# Main.net
KiCad netlist of a schematic drawn in Altium Designer
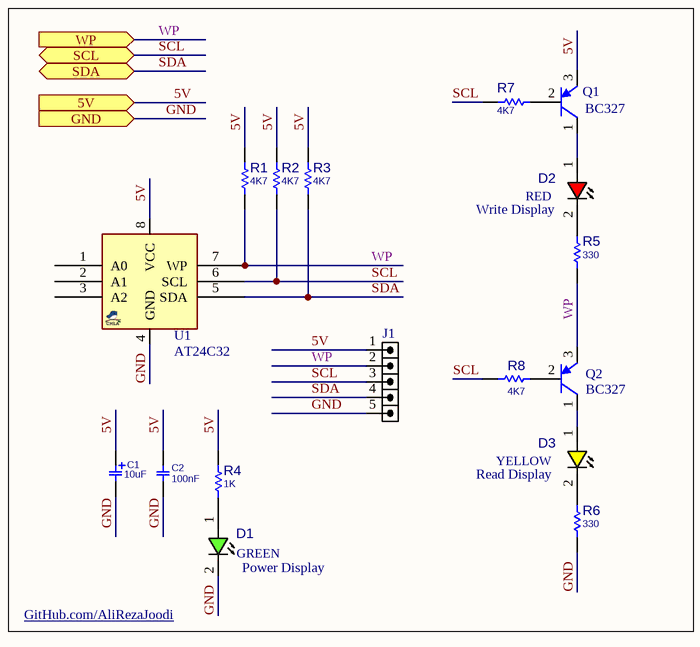
[diagram p0: Main.SchDoc]

(export (version "E")
  (design (tool "Eeschema 10.0.6"))
  (components
    (comp (ref "C1")
      (value "10uF")
      (footprint "C_EL_6X11")
      (description "CAP, THD, ELEC, 10uF, 25V")
      (fields (field (name "MANF") "MANF") (field (name "MANF_P#") "MANF_PART#"))
      (libsource (lib "CapElect_passive") (part "CAP_THD_EL_10u25V"))
    )
    (comp (ref "C2")
      (value "100nF")
      (footprint "C_CER_D3")
      (description "CAP, THD, CER MULTI LAYER,")
      (fields (field (name "MANF_P#") "MANF_PART#") (field (name "MANF") "MANF"))
      (libsource (lib "CapCer_passive") (part "CAP_THD_CERML"))
    )
    (comp (ref "D1")
      (value "GREEN")
      (footprint "LED5MM_GRN")
      (description "LED, THD, 5MM, GREEN")
      (fields (field (name "MANF") "MANF") (field (name "MANF_P#") "MANF_PART#"))
      (libsource (lib "led(diode)") (part "LED_THD_5MM_GRN"))
    )
    (comp (ref "D2")
      (value "RED")
      (footprint "LED5MM_RED")
      (description "LED, THD, 5MM, RED")
      (libsource (lib "led(diode)") (part "LED_THD_5MM_RED"))
    )
    (comp (ref "D3")
      (value "YELLOW")
      (footprint "LED5MM_YLW")
      (description "LED, THD, 5MM, YELLOW")
      (libsource (lib "led(diode)") (part "LED_THD_5MM_YLW"))
    )
    (comp (ref "J1")
      (value "HDR1X5")
      (footprint "HDR_M_1X5")
      (description "CONN, HEADER, Male, pitch: 2.54mm, 5POS")
      (libsource (lib "conn_header_2.54_st") (part "HDR_M_1X5"))
    )
    (comp (ref "Q1")
      (value "BC327")
      (footprint "TO92_3A")
      (description "BJT, PNP, 45v, 0.1A, THD, TO92")
      (fields (field (name "MANF_P#") "BC557") (field (name "MANF") "MULTICOMP"))
      (libsource (lib "transistor_bjt") (part "PNP_BC557_TO92"))
    )
    (comp (ref "Q2")
      (value "BC327")
      (footprint "TO92_3A")
      (description "BJT, PNP, 45v, 0.1A, THD, TO92")
      (fields (field (name "MANF_P#") "BC557") (field (name "MANF") "MULTICOMP"))
      (libsource (lib "transistor_bjt") (part "PNP_BC557_TO92"))
    )
    (comp (ref "R1")
      (value "4K7")
      (footprint "R025W_AX04")
      (description "RESISTOR, THD")
      (fields (field (name "MANF_P#") "RK73H1ETTP4701F") (field (name "MANF") "KOA SPEER"))
      (libsource (lib "passive_thd") (part "RES_THD"))
    )
    (comp (ref "R2")
      (value "4K7")
      (footprint "R025W_AX04")
      (description "RESISTOR, THD")
      (fields (field (name "MANF_P#") "RK73H1ETTP4701F") (field (name "MANF") "KOA SPEER"))
      (libsource (lib "passive_thd") (part "RES_THD"))
    )
    (comp (ref "R3")
      (value "4K7")
      (footprint "R025W_AX04")
      (description "RESISTOR, THD")
      (fields (field (name "MANF_P#") "RK73H1ETTP4701F") (field (name "MANF") "KOA SPEER"))
      (libsource (lib "passive_thd") (part "RES_THD"))
    )
    (comp (ref "R4")
      (value "1K")
      (footprint "R025W_AX04")
      (description "RESISTOR, THD")
      (fields (field (name "MANF_P#") "RK73H1ETTP4701F") (field (name "MANF") "KOA SPEER"))
      (libsource (lib "passive_thd") (part "RES_THD"))
    )
    (comp (ref "R5")
      (value "330")
      (footprint "R025W_AX04")
      (description "RESISTOR, THD")
      (fields (field (name "MANF_P#") "RK73H1ETTP4701F") (field (name "MANF") "KOA SPEER"))
      (libsource (lib "passive_thd") (part "RES_THD"))
    )
    (comp (ref "R6")
      (value "330")
      (footprint "R025W_AX04")
      (description "RESISTOR, THD")
      (fields (field (name "MANF_P#") "RK73H1ETTP4701F") (field (name "MANF") "KOA SPEER"))
      (libsource (lib "passive_thd") (part "RES_THD"))
    )
    (comp (ref "R7")
      (value "4K7")
      (footprint "R025W_AX04")
      (description "RESISTOR, THD")
      (fields (field (name "MANF_P#") "RK73H1ETTP4701F") (field (name "MANF") "KOA SPEER"))
      (libsource (lib "passive_thd") (part "RES_THD"))
    )
    (comp (ref "R8")
      (value "4K7")
      (footprint "R025W_AX04")
      (description "RESISTOR, THD")
      (fields (field (name "MANF_P#") "RK73H1ETTP4701F") (field (name "MANF") "KOA SPEER"))
      (libsource (lib "passive_thd") (part "RES_THD"))
    )
    (comp (ref "U1")
      (value "AT24C32")
      (footprint "DIP_8")
      (description "EEPROM, I2C, 64Kbit (8K X8)")
      (fields (field (name "MANF") "ON") (field (name "MANF_P#") "CAT24C64LI-G"))
      (libsource (lib "memory_eeprom_I2C") (part "EEPROM_I2C_CAT24C64_DIP8"))
    )
  )
  (nets
    (net (code "1") (name "/5V") (class "Default")
      (node (ref "C1") (pin "1") (pinfunction "1_1") (pintype "passive"))
      (node (ref "C2") (pin "2") (pinfunction "2_2") (pintype "passive"))
      (node (ref "J1") (pin "1") (pinfunction "1_1") (pintype "passive"))
      (node (ref "Q1") (pin "3") (pinfunction "E_3") (pintype "passive"))
      (node (ref "R1") (pin "2") (pinfunction "2_2") (pintype "passive"))
      (node (ref "R2") (pin "2") (pinfunction "2_2") (pintype "passive"))
      (node (ref "R3") (pin "2") (pinfunction "2_2") (pintype "passive"))
      (node (ref "R4") (pin "2") (pinfunction "2_2") (pintype "passive"))
      (node (ref "U1") (pin "8") (pinfunction "VCC_8") (pintype "passive"))
    )
    (net (code "2") (name "/GND") (class "Default")
      (node (ref "C1") (pin "2") (pinfunction "2_2") (pintype "passive"))
      (node (ref "C2") (pin "1") (pinfunction "1_1") (pintype "passive"))
      (node (ref "D1") (pin "2") (pinfunction "CATHODE_2") (pintype "passive"))
      (node (ref "J1") (pin "5") (pinfunction "5_5") (pintype "passive"))
      (node (ref "R6") (pin "2") (pinfunction "2_2") (pintype "passive"))
      (node (ref "U1") (pin "4") (pinfunction "GND_4") (pintype "passive"))
    )
    (net (code "3") (name "/SCL") (class "Default")
      (node (ref "J1") (pin "3") (pinfunction "3_3") (pintype "passive"))
      (node (ref "R2") (pin "1") (pinfunction "1_1") (pintype "passive"))
      (node (ref "R7") (pin "2") (pinfunction "2_2") (pintype "passive"))
      (node (ref "R8") (pin "2") (pinfunction "2_2") (pintype "passive"))
      (node (ref "U1") (pin "6") (pinfunction "SCL_6") (pintype "passive"))
    )
    (net (code "4") (name "/SDA") (class "Default")
      (node (ref "J1") (pin "4") (pinfunction "4_4") (pintype "passive"))
      (node (ref "R3") (pin "1") (pinfunction "1_1") (pintype "passive"))
      (node (ref "U1") (pin "5") (pinfunction "SDA_5") (pintype "passive"))
    )
    (net (code "5") (name "/WP") (class "Default")
      (node (ref "J1") (pin "2") (pinfunction "2_2") (pintype "passive"))
      (node (ref "Q2") (pin "3") (pinfunction "E_3") (pintype "passive"))
      (node (ref "R1") (pin "1") (pinfunction "1_1") (pintype "passive"))
      (node (ref "R5") (pin "2") (pinfunction "2_2") (pintype "passive"))
      (node (ref "U1") (pin "7") (pinfunction "WP_7") (pintype "passive"))
    )
    (net (code "6") (name "Net-(D1-ANODE)") (class "Default")
      (node (ref "D1") (pin "1") (pinfunction "ANODE_1") (pintype "passive"))
      (node (ref "R4") (pin "1") (pinfunction "1_1") (pintype "passive"))
    )
    (net (code "7") (name "Net-(D2-ANODE)") (class "Default")
      (node (ref "D2") (pin "1") (pinfunction "ANODE_1") (pintype "passive"))
      (node (ref "Q1") (pin "1") (pinfunction "C_1") (pintype "passive"))
    )
    (net (code "8") (name "Net-(D2-CATHODE)") (class "Default")
      (node (ref "D2") (pin "2") (pinfunction "CATHODE_2") (pintype "passive"))
      (node (ref "R5") (pin "1") (pinfunction "1_1") (pintype "passive"))
    )
    (net (code "9") (name "Net-(D3-ANODE)") (class "Default")
      (node (ref "D3") (pin "1") (pinfunction "ANODE_1") (pintype "passive"))
      (node (ref "Q2") (pin "1") (pinfunction "C_1") (pintype "passive"))
    )
    (net (code "10") (name "Net-(D3-CATHODE)") (class "Default")
      (node (ref "D3") (pin "2") (pinfunction "CATHODE_2") (pintype "passive"))
      (node (ref "R6") (pin "1") (pinfunction "1_1") (pintype "passive"))
    )
    (net (code "11") (name "Net-(Q1-B)") (class "Default")
      (node (ref "Q1") (pin "2") (pinfunction "B_2") (pintype "passive"))
      (node (ref "R7") (pin "1") (pinfunction "1_1") (pintype "passive"))
    )
    (net (code "12") (name "Net-(Q2-B)") (class "Default")
      (node (ref "Q2") (pin "2") (pinfunction "B_2") (pintype "passive"))
      (node (ref "R8") (pin "1") (pinfunction "1_1") (pintype "passive"))
    )
    (net (code "13") (name "unconnected-(U1-A0-Pad1)") (class "Default")
      (node (ref "U1") (pin "1") (pinfunction "A0_1") (pintype "passive"))
    )
    (net (code "14") (name "unconnected-(U1-A1-Pad2)") (class "Default")
      (node (ref "U1") (pin "2") (pinfunction "A1_2") (pintype "passive"))
    )
    (net (code "15") (name "unconnected-(U1-A2-Pad3)") (class "Default")
      (node (ref "U1") (pin "3") (pinfunction "A2_3") (pintype "passive"))
    )
  )
)
